# ProPrj_SmartOvi_v1_2025-12-15.net
KiCad netlist of a schematic drawn in EasyEDA Pro
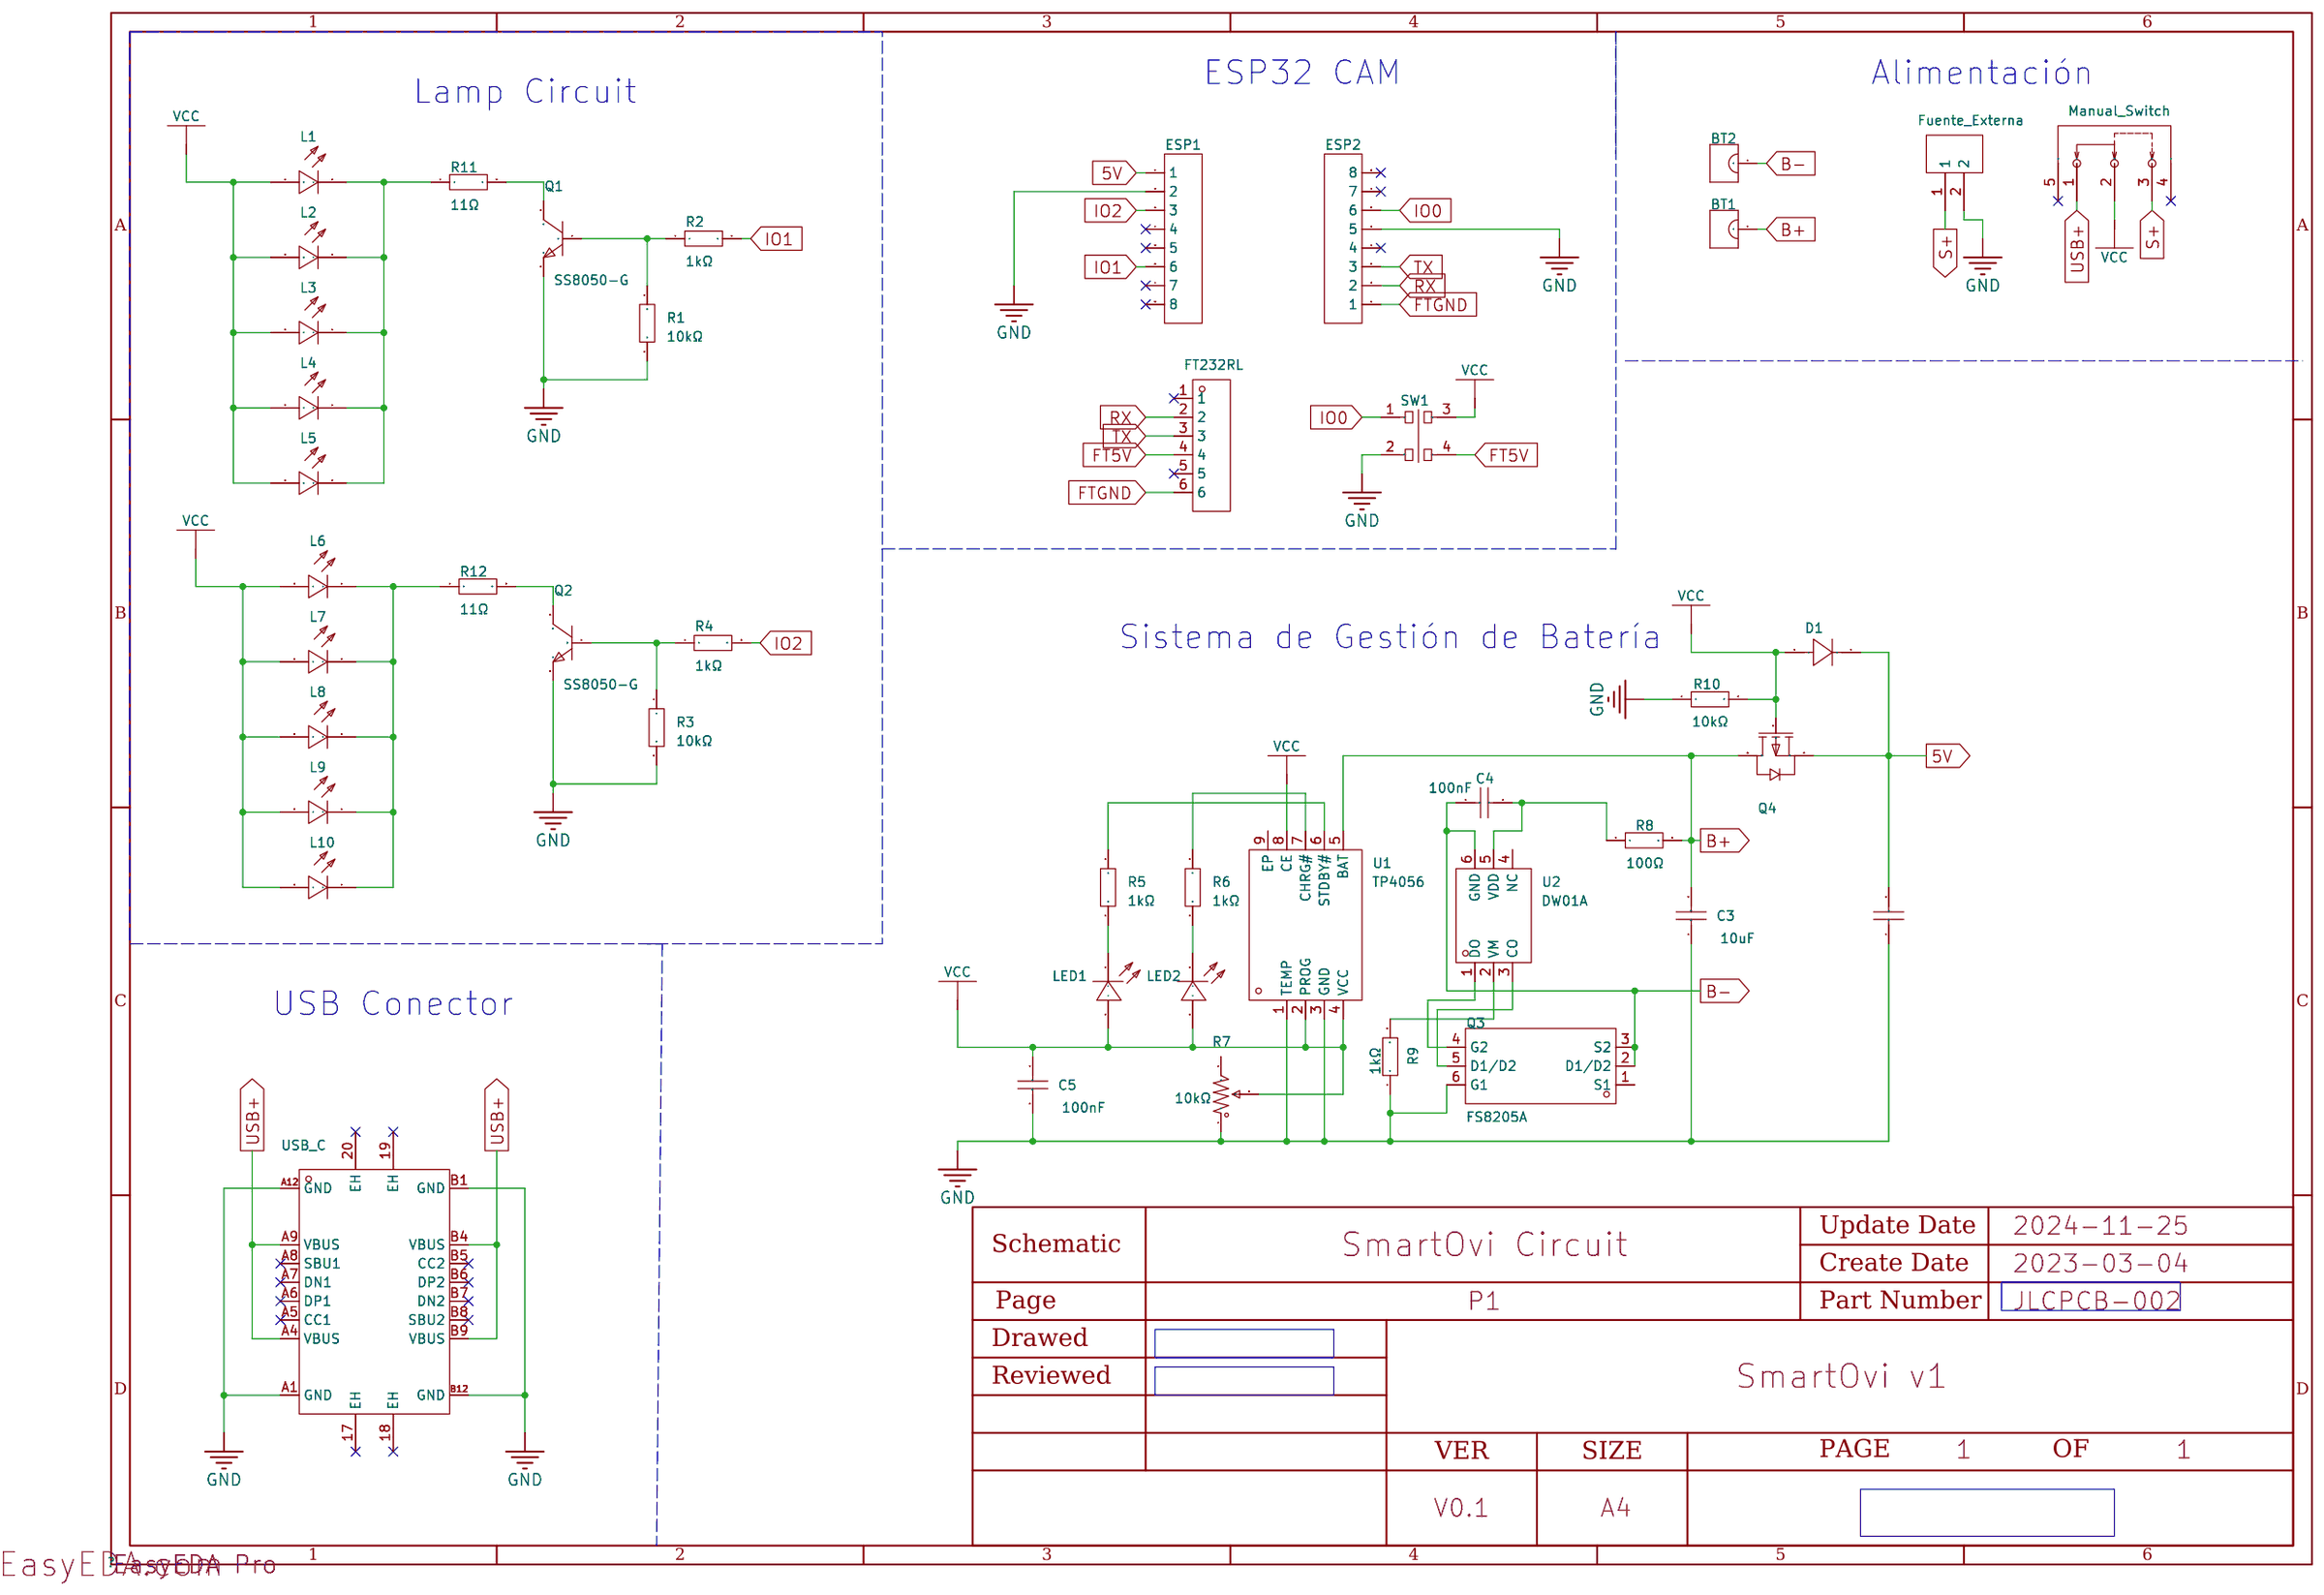
[diagram p0: schematic sheet]

(export (version "E")
  (design (tool "Eeschema 10.0.6"))
  (components
    (comp (ref "BT1")
      (value "MY-18650-01")
      (footprint "easyedapro:BAT-TH_MY-18650-01")
      (fields (field (name "Manufacturer") "MYOUNG(美阳)"))
      (libsource (lib "easyedapro") (part "MY-18650-01"))
    )
    (comp (ref "BT2")
      (value "MY-18650-01")
      (footprint "easyedapro:BAT-TH_MY-18650-01")
      (fields (field (name "Manufacturer") "MYOUNG(美阳)"))
      (libsource (lib "easyedapro") (part "MY-18650-01"))
    )
    (comp (ref "C1")
      (value "10uF")
      (footprint "easyedapro:C0805")
      (fields
        (field (name "Manufacturer Part") "CL21A106KPFNNNE")
        (field (name "Manufacturer") "SAMSUNG(三星)")
      )
      (libsource (lib "easyedapro") (part "CL21A106KPFNNNE"))
    )
    (comp (ref "C3")
      (value "10uF")
      (footprint "easyedapro:C0805")
      (fields
        (field (name "Manufacturer Part") "CL21A106KPFNNNE")
        (field (name "Manufacturer") "SAMSUNG(三星)")
      )
      (libsource (lib "easyedapro") (part "CL21A106KPFNNNE"))
    )
    (comp (ref "C4")
      (value "100nF")
      (footprint "easyedapro:C0805")
      (fields (field (name "Manufacturer Part") "0805B104K500NT") (field (name "Manufacturer") "FH(风华)"))
      (libsource (lib "easyedapro") (part "0805B104K500NT"))
    )
    (comp (ref "C5")
      (value "100nF")
      (footprint "easyedapro:C0805")
      (fields (field (name "Manufacturer Part") "0805B104K500NT") (field (name "Manufacturer") "FH(风华)"))
      (libsource (lib "easyedapro") (part "0805B104K500NT"))
    )
    (comp (ref "D1")
      (value "VS-90EPS16L-M3")
      (footprint "easyedapro:TO-247AD-2_L16.0-W5.0-P10.92-L")
      (fields (field (name "Manufacturer") "VISHAY(威世)"))
      (libsource (lib "easyedapro") (part "VS-90EPS16L-M3"))
    )
    (comp (ref "ESP1")
      (value "2.54-1*8P母环保")
      (footprint "easyedapro:HDR-TH_8P-P2.54-V-F-1")
      (fields (field (name "Manufacturer") "BOOMELE(博穆精密)"))
      (libsource (lib "easyedapro") (part "Header-Female-2.54_1x8"))
    )
    (comp (ref "ESP2")
      (value "2.54-1*8P母环保")
      (footprint "easyedapro:HDR-TH_8P-P2.54-V-F-1")
      (fields (field (name "Manufacturer") "BOOMELE(博穆精密)"))
      (libsource (lib "easyedapro") (part "Header-Female-2.54_1x8"))
    )
    (comp (ref "FT232RL")
      (value "2.54-1*6P母")
      (footprint "easyedapro:HDR-TH_6P-P2.54-V-F")
      (fields (field (name "Manufacturer") "BOOMELE(博穆精密)"))
      (libsource (lib "easyedapro") (part "Header-Female-2.54_1x6"))
    )
    (comp (ref "Fuente_Externa")
      (value "WJ500V-5.08-2P")
      (footprint "easyedapro:CONN-TH_2P-P5.00_WJ500V-5.08-2P")
      (fields (field (name "Manufacturer") "KANGNEX(康奈克斯电气)"))
      (libsource (lib "easyedapro") (part "WJ500V-5.08-2P-14-00A"))
    )
    (comp (ref "L1")
      (value "MHL5013UGDWT")
      (footprint "easyedapro:LED-TH_BD5.8-P2.54-RD")
      (fields (field (name "Manufacturer") "MEIHUA(美华)"))
      (libsource (lib "easyedapro") (part "MHL5013UGDWT"))
    )
    (comp (ref "L2")
      (value "MHL5013UGDWT")
      (footprint "easyedapro:LED-TH_BD5.8-P2.54-RD")
      (fields (field (name "Manufacturer") "MEIHUA(美华)"))
      (libsource (lib "easyedapro") (part "MHL5013UGDWT"))
    )
    (comp (ref "L3")
      (value "MHL5013UGDWT")
      (footprint "easyedapro:LED-TH_BD5.8-P2.54-RD")
      (fields (field (name "Manufacturer") "MEIHUA(美华)"))
      (libsource (lib "easyedapro") (part "MHL5013UGDWT"))
    )
    (comp (ref "L4")
      (value "MHL5013UGDWT")
      (footprint "easyedapro:LED-TH_BD5.8-P2.54-RD")
      (fields (field (name "Manufacturer") "MEIHUA(美华)"))
      (libsource (lib "easyedapro") (part "MHL5013UGDWT"))
    )
    (comp (ref "L5")
      (value "MHL5013UGDWT")
      (footprint "easyedapro:LED-TH_BD5.8-P2.54-RD")
      (fields (field (name "Manufacturer") "MEIHUA(美华)"))
      (libsource (lib "easyedapro") (part "MHL5013UGDWT"))
    )
    (comp (ref "L6")
      (value "MHL5013UGDWT")
      (footprint "easyedapro:LED-TH_BD5.8-P2.54-RD")
      (fields (field (name "Manufacturer") "MEIHUA(美华)"))
      (libsource (lib "easyedapro") (part "MHL5013UGDWT"))
    )
    (comp (ref "L7")
      (value "MHL5013UGDWT")
      (footprint "easyedapro:LED-TH_BD5.8-P2.54-RD")
      (fields (field (name "Manufacturer") "MEIHUA(美华)"))
      (libsource (lib "easyedapro") (part "MHL5013UGDWT"))
    )
    (comp (ref "L8")
      (value "MHL5013UGDWT")
      (footprint "easyedapro:LED-TH_BD5.8-P2.54-RD")
      (fields (field (name "Manufacturer") "MEIHUA(美华)"))
      (libsource (lib "easyedapro") (part "MHL5013UGDWT"))
    )
    (comp (ref "L9")
      (value "MHL5013UGDWT")
      (footprint "easyedapro:LED-TH_BD5.8-P2.54-RD")
      (fields (field (name "Manufacturer") "MEIHUA(美华)"))
      (libsource (lib "easyedapro") (part "MHL5013UGDWT"))
    )
    (comp (ref "L10")
      (value "MHL5013UGDWT")
      (footprint "easyedapro:LED-TH_BD5.8-P2.54-RD")
      (fields (field (name "Manufacturer") "MEIHUA(美华)"))
      (libsource (lib "easyedapro") (part "MHL5013UGDWT"))
    )
    (comp (ref "LED1")
      (value "NCD0805R1")
      (footprint "easyedapro:LED0805-RD")
      (description "Emitted Color:红灯")
      (fields (field (name "Manufacturer") "国星光电"))
      (libsource (lib "easyedapro") (part "FC-2012HRK-620D"))
    )
    (comp (ref "LED2")
      (value "NCD0805B2")
      (footprint "easyedapro:LED0805-RD")
      (description "Emitted Color:blue")
      (fields (field (name "Manufacturer") "国星光电"))
      (libsource (lib "easyedapro") (part "FC-A2012BK-470H2"))
    )
    (comp (ref "Manual_Switch")
      (value "SK12D07VG4")
      (footprint "easyedapro:SW-TH_SK12D07VG4")
      (fields (field (name "Manufacturer") "SHOU HAN(首韩)"))
      (libsource (lib "easyedapro") (part "SK12D07VG4"))
    )
    (comp (ref "Q1")
      (value "SS8050-G")
      (footprint "easyedapro:SOT-23-3_L2.9-W1.6-P1.90-LS2.8-BR")
      (fields (field (name "Manufacturer") "CJ(江苏长电/长晶)"))
      (libsource (lib "easyedapro") (part "SS8050-G"))
    )
    (comp (ref "Q2")
      (value "SS8050-G")
      (footprint "easyedapro:SOT-23-3_L2.9-W1.6-P1.90-LS2.8-BR")
      (fields (field (name "Manufacturer") "CJ(江苏长电/长晶)"))
      (libsource (lib "easyedapro") (part "SS8050-G"))
    )
    (comp (ref "Q3")
      (value "FS8205A")
      (footprint "easyedapro:SOT-23-6_L2.9-W1.6-P0.95-LS2.8-BR")
      (fields (field (name "Manufacturer") "FUXINSEMI(富芯森美)"))
      (libsource (lib "easyedapro") (part "FS8205A_C908265"))
    )
    (comp (ref "Q4")
      (value "AO3401A")
      (footprint "easyedapro:SOT-23_L2.9-W1.3-P1.90-LS2.4-BR")
      (fields (field (name "Manufacturer") "UMW(广东友台半导体)"))
      (libsource (lib "easyedapro") (part "AO3401A_C347476"))
    )
    (comp (ref "R1")
      (value "10kΩ")
      (footprint "easyedapro:R0805")
      (fields
        (field (name "Manufacturer Part") "0805W8J0103T5E")
        (field (name "Manufacturer") "UNI-ROYAL(厚声)")
      )
      (libsource (lib "easyedapro") (part "0805W8J0103T5E"))
    )
    (comp (ref "R2")
      (value "1kΩ")
      (footprint "easyedapro:R0805")
      (fields
        (field (name "Manufacturer Part") "0805W8J0102T5E")
        (field (name "Manufacturer") "UNI-ROYAL(厚声)")
      )
      (libsource (lib "easyedapro") (part "0805W8J0102T5E"))
    )
    (comp (ref "R3")
      (value "10kΩ")
      (footprint "easyedapro:R0805")
      (fields
        (field (name "Manufacturer Part") "0805W8J0103T5E")
        (field (name "Manufacturer") "UNI-ROYAL(厚声)")
      )
      (libsource (lib "easyedapro") (part "0805W8J0103T5E"))
    )
    (comp (ref "R4")
      (value "1kΩ")
      (footprint "easyedapro:R0805")
      (fields
        (field (name "Manufacturer Part") "0805W8J0102T5E")
        (field (name "Manufacturer") "UNI-ROYAL(厚声)")
      )
      (libsource (lib "easyedapro") (part "0805W8J0102T5E"))
    )
    (comp (ref "R5")
      (value "1kΩ")
      (footprint "easyedapro:R0805")
      (fields
        (field (name "Manufacturer Part") "0805W8J0102T5E")
        (field (name "Manufacturer") "UNI-ROYAL(厚声)")
      )
      (libsource (lib "easyedapro") (part "0805W8J0102T5E"))
    )
    (comp (ref "R6")
      (value "1kΩ")
      (footprint "easyedapro:R0805")
      (fields
        (field (name "Manufacturer Part") "0805W8J0102T5E")
        (field (name "Manufacturer") "UNI-ROYAL(厚声)")
      )
      (libsource (lib "easyedapro") (part "0805W8J0102T5E"))
    )
    (comp (ref "R7")
      (value "10kΩ")
      (footprint "easyedapro:RES-ADJ-SMD_3P-L3.0-W3.8-P1.75-BR")
      (description "Resistance: Tolerance:±25% Tolerance:±25% Power(Watts):150mW Turns:- Rated Voltage:-")
      (fields (field (name "Manufacturer Part") "TC33X-2-103E") (field (name "Manufacturer") "BOURNS"))
      (libsource (lib "easyedapro") (part "TC33X-2-103E"))
    )
    (comp (ref "R8")
      (value "100Ω")
      (footprint "easyedapro:R0805")
      (fields (field (name "Manufacturer Part") "RTT05101JTP") (field (name "Manufacturer") "RALEC(旺诠)"))
      (libsource (lib "easyedapro") (part "RTT05101JTP"))
    )
    (comp (ref "R9")
      (value "1kΩ")
      (footprint "easyedapro:R0805")
      (fields
        (field (name "Manufacturer Part") "0805W8J0102T5E")
        (field (name "Manufacturer") "UNI-ROYAL(厚声)")
      )
      (libsource (lib "easyedapro") (part "0805W8J0102T5E"))
    )
    (comp (ref "R10")
      (value "10kΩ")
      (footprint "easyedapro:R0805")
      (fields
        (field (name "Manufacturer Part") "0805W8J0103T5E")
        (field (name "Manufacturer") "UNI-ROYAL(厚声)")
      )
      (libsource (lib "easyedapro") (part "0805W8J0103T5E"))
    )
    (comp (ref "R11")
      (value "11Ω")
      (footprint "easyedapro:R0805")
      (fields (field (name "Manufacturer Part") "AECR0805F11R0K9") (field (name "Manufacturer") "RESI(开步睿思)"))
      (libsource (lib "easyedapro") (part "AECR0805F11R0K9"))
    )
    (comp (ref "R12")
      (value "11Ω")
      (footprint "easyedapro:R0805")
      (fields (field (name "Manufacturer Part") "AECR0805F11R0K9") (field (name "Manufacturer") "RESI(开步睿思)"))
      (libsource (lib "easyedapro") (part "AECR0805F11R0K9"))
    )
    (comp (ref "SW1")
      (value "BTSA-L-P-11")
      (footprint "easyedapro:SW-TH_BTSA-X-P-11")
      (fields (field (name "Manufacturer") "ROCPU Switches(台普)"))
      (libsource (lib "easyedapro") (part "BTSA-N-P-11"))
    )
    (comp (ref "U1")
      (value "TP4056")
      (footprint "easyedapro:ESOP-8_L4.9-W3.9-P1.27-LS6.0-BL-EP")
      (fields (field (name "Manufacturer") "TECH PUBLIC(台舟)"))
      (libsource (lib "easyedapro") (part "TP4056_C5311018"))
    )
    (comp (ref "U2")
      (value "DW01A")
      (footprint "easyedapro:SOT-23-6_L2.9-W1.6-P0.95-LS2.8-BL")
      (fields (field (name "Manufacturer") "TF(拓锋)"))
      (libsource (lib "easyedapro") (part "DW01A_C436931"))
    )
    (comp (ref "USB_C")
      (value "TYPEC-306DDW-ARP16")
      (footprint "easyedapro:USB-C-TH_TYPEC-306DDW-ARP16")
      (fields (field (name "Manufacturer") "XUNPU(讯普)"))
      (libsource (lib "easyedapro") (part "TYPEC-306DDW-ARP16"))
    )
  )
  (nets
    (net (code "1") (name "5V") (class "Default")
      (node (ref "C1") (pin "2") (pinfunction "2_2") (pintype "input"))
      (node (ref "D1") (pin "1") (pinfunction "K_1") (pintype "unspecified"))
      (node (ref "ESP1") (pin "1") (pinfunction "1_1") (pintype "input"))
      (node (ref "Q4") (pin "2") (pinfunction "S_2") (pintype "input"))
    )
    (net (code "2") (name "B+") (class "Default")
      (node (ref "BT1") (pin "1") (pinfunction "1_1") (pintype "input"))
      (node (ref "C3") (pin "2") (pinfunction "2_2") (pintype "input"))
      (node (ref "Q4") (pin "3") (pinfunction "D_3") (pintype "input"))
      (node (ref "R8") (pin "2") (pinfunction "2_2") (pintype "input"))
      (node (ref "U1") (pin "5") (pinfunction "BAT_5") (pintype "input"))
    )
    (net (code "3") (name "B-") (class "Default")
      (node (ref "BT2") (pin "1") (pinfunction "1_1") (pintype "input"))
      (node (ref "C4") (pin "1") (pinfunction "1_1") (pintype "input"))
      (node (ref "Q3") (pin "2") (pinfunction "D1/D2_2") (pintype "input"))
      (node (ref "Q3") (pin "3") (pinfunction "S2_3") (pintype "input"))
      (node (ref "U2") (pin "6") (pinfunction "GND_6") (pintype "input"))
    )
    (net (code "4") (name "FT5V") (class "Default")
      (node (ref "FT232RL") (pin "4") (pinfunction "4_4") (pintype "input"))
      (node (ref "SW1") (pin "4") (pinfunction "4_4") (pintype "input"))
    )
    (net (code "5") (name "FTGND") (class "Default")
      (node (ref "ESP2") (pin "1") (pinfunction "1_1") (pintype "input"))
      (node (ref "FT232RL") (pin "6") (pinfunction "6_6") (pintype "input"))
    )
    (net (code "6") (name "GND") (class "Default")
      (node (ref "C1") (pin "1") (pinfunction "1_1") (pintype "input"))
      (node (ref "C3") (pin "1") (pinfunction "1_1") (pintype "input"))
      (node (ref "C5") (pin "2") (pinfunction "2_2") (pintype "input"))
      (node (ref "ESP1") (pin "2") (pinfunction "2_2") (pintype "input"))
      (node (ref "ESP2") (pin "5") (pinfunction "5_5") (pintype "input"))
      (node (ref "Fuente_Externa") (pin "2") (pinfunction "2_2") (pintype "input"))
      (node (ref "Q1") (pin "2") (pinfunction "E_2") (pintype "input"))
      (node (ref "Q2") (pin "2") (pinfunction "E_2") (pintype "input"))
      (node (ref "Q3") (pin "6") (pinfunction "G1_6") (pintype "input"))
      (node (ref "R1") (pin "2") (pinfunction "2_2") (pintype "input"))
      (node (ref "R10") (pin "1") (pinfunction "1_1") (pintype "input"))
      (node (ref "R3") (pin "2") (pinfunction "2_2") (pintype "input"))
      (node (ref "R7") (pin "1") (pinfunction "1_1") (pintype "input"))
      (node (ref "R9") (pin "1") (pinfunction "1_1") (pintype "input"))
      (node (ref "SW1") (pin "2") (pinfunction "2_2") (pintype "input"))
      (node (ref "U1") (pin "1") (pinfunction "TEMP_1") (pintype "input"))
      (node (ref "U1") (pin "3") (pinfunction "GND_3") (pintype "input"))
      (node (ref "USB_C") (pin "A1") (pinfunction "GND_A1") (pintype "input"))
      (node (ref "USB_C") (pin "A12") (pinfunction "GND_A12") (pintype "input"))
      (node (ref "USB_C") (pin "B1") (pinfunction "GND_B1") (pintype "input"))
      (node (ref "USB_C") (pin "B12") (pinfunction "GND_B12") (pintype "input"))
    )
    (net (code "7") (name "IO0") (class "Default")
      (node (ref "ESP2") (pin "6") (pinfunction "6_6") (pintype "input"))
      (node (ref "SW1") (pin "1") (pinfunction "1_1") (pintype "input"))
    )
    (net (code "8") (name "IO1") (class "Default")
      (node (ref "ESP1") (pin "6") (pinfunction "6_6") (pintype "input"))
      (node (ref "R2") (pin "2") (pinfunction "2_2") (pintype "input"))
    )
    (net (code "9") (name "IO2") (class "Default")
      (node (ref "ESP1") (pin "3") (pinfunction "3_3") (pintype "input"))
      (node (ref "R4") (pin "2") (pinfunction "2_2") (pintype "input"))
    )
    (net (code "10") (name "Net-(L1-K)") (class "Default")
      (node (ref "L1") (pin "1") (pinfunction "K_1") (pintype "input"))
      (node (ref "L2") (pin "1") (pinfunction "K_1") (pintype "input"))
      (node (ref "L3") (pin "1") (pinfunction "K_1") (pintype "input"))
      (node (ref "L4") (pin "1") (pinfunction "K_1") (pintype "input"))
      (node (ref "L5") (pin "1") (pinfunction "K_1") (pintype "input"))
      (node (ref "R11") (pin "1") (pinfunction "1_1") (pintype "unspecified"))
    )
    (net (code "11") (name "Net-(L10-K)") (class "Default")
      (node (ref "L10") (pin "1") (pinfunction "K_1") (pintype "input"))
      (node (ref "L6") (pin "1") (pinfunction "K_1") (pintype "input"))
      (node (ref "L7") (pin "1") (pinfunction "K_1") (pintype "input"))
      (node (ref "L8") (pin "1") (pinfunction "K_1") (pintype "input"))
      (node (ref "L9") (pin "1") (pinfunction "K_1") (pintype "input"))
      (node (ref "R12") (pin "1") (pinfunction "1_1") (pintype "unspecified"))
    )
    (net (code "12") (name "Net-(LED1--)") (class "Default")
      (node (ref "LED1") (pin "1") (pinfunction "-_1") (pintype "input"))
      (node (ref "R5") (pin "1") (pinfunction "1_1") (pintype "input"))
    )
    (net (code "13") (name "Net-(LED2--)") (class "Default")
      (node (ref "LED2") (pin "1") (pinfunction "-_1") (pintype "input"))
      (node (ref "R6") (pin "1") (pinfunction "1_1") (pintype "input"))
    )
    (net (code "14") (name "Net-(Q1-B)") (class "Default")
      (node (ref "Q1") (pin "1") (pinfunction "B_1") (pintype "input"))
      (node (ref "R1") (pin "1") (pinfunction "1_1") (pintype "input"))
      (node (ref "R2") (pin "1") (pinfunction "1_1") (pintype "input"))
    )
    (net (code "15") (name "Net-(Q1-C)") (class "Default")
      (node (ref "Q1") (pin "3") (pinfunction "C_3") (pintype "input"))
      (node (ref "R11") (pin "2") (pinfunction "2_2") (pintype "unspecified"))
    )
    (net (code "16") (name "Net-(Q2-B)") (class "Default")
      (node (ref "Q2") (pin "1") (pinfunction "B_1") (pintype "input"))
      (node (ref "R3") (pin "1") (pinfunction "1_1") (pintype "input"))
      (node (ref "R4") (pin "1") (pinfunction "1_1") (pintype "input"))
    )
    (net (code "17") (name "Net-(Q2-C)") (class "Default")
      (node (ref "Q2") (pin "3") (pinfunction "C_3") (pintype "input"))
      (node (ref "R12") (pin "2") (pinfunction "2_2") (pintype "unspecified"))
    )
    (net (code "18") (name "Net-(Q3-G2)") (class "Default")
      (node (ref "Q3") (pin "4") (pinfunction "G2_4") (pintype "input"))
      (node (ref "U2") (pin "1") (pinfunction "DO_1") (pintype "input"))
    )
    (net (code "19") (name "Net-(U1-CHRG#)") (class "Default")
      (node (ref "R6") (pin "2") (pinfunction "2_2") (pintype "input"))
      (node (ref "U1") (pin "7") (pinfunction "CHRG#_7") (pintype "input"))
    )
    (net (code "20") (name "Net-(U1-STDBY#)") (class "Default")
      (node (ref "R5") (pin "2") (pinfunction "2_2") (pintype "input"))
      (node (ref "U1") (pin "6") (pinfunction "STDBY#_6") (pintype "input"))
    )
    (net (code "21") (name "Net-(U2-CO)") (class "Default")
      (node (ref "Q3") (pin "5") (pinfunction "D1/D2_5") (pintype "input"))
      (node (ref "U2") (pin "3") (pinfunction "CO_3") (pintype "input"))
    )
    (net (code "22") (name "Net-(U2-VDD)") (class "Default")
      (node (ref "C4") (pin "2") (pinfunction "2_2") (pintype "input"))
      (node (ref "R8") (pin "1") (pinfunction "1_1") (pintype "input"))
      (node (ref "U2") (pin "5") (pinfunction "VDD_5") (pintype "input"))
    )
    (net (code "23") (name "Net-(U2-VM)") (class "Default")
      (node (ref "R9") (pin "2") (pinfunction "2_2") (pintype "input"))
      (node (ref "U2") (pin "2") (pinfunction "VM_2") (pintype "input"))
    )
    (net (code "24") (name "RX") (class "Default")
      (node (ref "ESP2") (pin "2") (pinfunction "2_2") (pintype "input"))
      (node (ref "FT232RL") (pin "2") (pinfunction "2_2") (pintype "input"))
    )
    (net (code "25") (name "S+") (class "Default")
      (node (ref "Fuente_Externa") (pin "1") (pinfunction "1_1") (pintype "input"))
      (node (ref "Manual_Switch") (pin "3") (pinfunction "3_3") (pintype "input"))
    )
    (net (code "26") (name "TX") (class "Default")
      (node (ref "ESP2") (pin "3") (pinfunction "3_3") (pintype "input"))
      (node (ref "FT232RL") (pin "3") (pinfunction "3_3") (pintype "input"))
    )
    (net (code "27") (name "USB+") (class "Default")
      (node (ref "Manual_Switch") (pin "1") (pinfunction "1_1") (pintype "input"))
      (node (ref "USB_C") (pin "A4") (pinfunction "VBUS_A4") (pintype "input"))
      (node (ref "USB_C") (pin "A9") (pinfunction "VBUS_A9") (pintype "input"))
      (node (ref "USB_C") (pin "B4") (pinfunction "VBUS_B4") (pintype "input"))
      (node (ref "USB_C") (pin "B9") (pinfunction "VBUS_B9") (pintype "input"))
    )
    (net (code "28") (name "VCC") (class "Default")
      (node (ref "C5") (pin "1") (pinfunction "1_1") (pintype "input"))
      (node (ref "D1") (pin "3") (pinfunction "A_3") (pintype "unspecified"))
      (node (ref "L1") (pin "2") (pinfunction "A_2") (pintype "input"))
      (node (ref "L10") (pin "2") (pinfunction "A_2") (pintype "input"))
      (node (ref "L2") (pin "2") (pinfunction "A_2") (pintype "input"))
      (node (ref "L3") (pin "2") (pinfunction "A_2") (pintype "input"))
      (node (ref "L4") (pin "2") (pinfunction "A_2") (pintype "input"))
      (node (ref "L5") (pin "2") (pinfunction "A_2") (pintype "input"))
      (node (ref "L6") (pin "2") (pinfunction "A_2") (pintype "input"))
      (node (ref "L7") (pin "2") (pinfunction "A_2") (pintype "input"))
      (node (ref "L8") (pin "2") (pinfunction "A_2") (pintype "input"))
      (node (ref "L9") (pin "2") (pinfunction "A_2") (pintype "input"))
      (node (ref "LED1") (pin "2") (pinfunction "+_2") (pintype "input"))
      (node (ref "LED2") (pin "2") (pinfunction "+_2") (pintype "input"))
      (node (ref "Manual_Switch") (pin "2") (pinfunction "2_2") (pintype "input"))
      (node (ref "Q4") (pin "1") (pinfunction "G_1") (pintype "input"))
      (node (ref "R10") (pin "2") (pinfunction "2_2") (pintype "input"))
      (node (ref "R7") (pin "2") (pinfunction "2_2") (pintype "input"))
      (node (ref "SW1") (pin "3") (pinfunction "3_3") (pintype "input"))
      (node (ref "U1") (pin "2") (pinfunction "PROG_2") (pintype "input"))
      (node (ref "U1") (pin "4") (pinfunction "VCC_4") (pintype "input"))
      (node (ref "U1") (pin "8") (pinfunction "CE_8") (pintype "input"))
    )
    (net (code "29") (name "unconnected-(ESP1-Pad4)") (class "Default")
      (node (ref "ESP1") (pin "4") (pinfunction "4_4") (pintype "input+no_connect"))
    )
    (net (code "30") (name "unconnected-(ESP1-Pad5)") (class "Default")
      (node (ref "ESP1") (pin "5") (pinfunction "5_5") (pintype "input+no_connect"))
    )
    (net (code "31") (name "unconnected-(ESP1-Pad7)") (class "Default")
      (node (ref "ESP1") (pin "7") (pinfunction "7_7") (pintype "input+no_connect"))
    )
    (net (code "32") (name "unconnected-(ESP1-Pad8)") (class "Default")
      (node (ref "ESP1") (pin "8") (pinfunction "8_8") (pintype "input+no_connect"))
    )
    (net (code "33") (name "unconnected-(ESP2-Pad4)") (class "Default")
      (node (ref "ESP2") (pin "4") (pinfunction "4_4") (pintype "input+no_connect"))
    )
    (net (code "34") (name "unconnected-(ESP2-Pad7)") (class "Default")
      (node (ref "ESP2") (pin "7") (pinfunction "7_7") (pintype "input+no_connect"))
    )
    (net (code "35") (name "unconnected-(ESP2-Pad8)") (class "Default")
      (node (ref "ESP2") (pin "8") (pinfunction "8_8") (pintype "input+no_connect"))
    )
    (net (code "36") (name "unconnected-(FT232RL-Pad1)") (class "Default")
      (node (ref "FT232RL") (pin "1") (pinfunction "1_1") (pintype "input+no_connect"))
    )
    (net (code "37") (name "unconnected-(FT232RL-Pad5)") (class "Default")
      (node (ref "FT232RL") (pin "5") (pinfunction "5_5") (pintype "input+no_connect"))
    )
    (net (code "38") (name "unconnected-(Manual_Switch-Pad4)") (class "Default")
      (node (ref "Manual_Switch") (pin "4") (pinfunction "4_4") (pintype "input+no_connect"))
    )
    (net (code "39") (name "unconnected-(Manual_Switch-Pad5)") (class "Default")
      (node (ref "Manual_Switch") (pin "5") (pinfunction "5_5") (pintype "input+no_connect"))
    )
    (net (code "40") (name "unconnected-(Q3-S1-Pad1)") (class "Default")
      (node (ref "Q3") (pin "1") (pinfunction "S1_1") (pintype "input"))
    )
    (net (code "41") (name "unconnected-(R7-Pad3)") (class "Default")
      (node (ref "R7") (pin "3") (pinfunction "3_3") (pintype "input"))
    )
    (net (code "42") (name "unconnected-(U1-EP-Pad9)") (class "Default")
      (node (ref "U1") (pin "9") (pinfunction "EP_9") (pintype "input"))
    )
    (net (code "43") (name "unconnected-(U2-NC-Pad4)") (class "Default")
      (node (ref "U2") (pin "4") (pinfunction "NC_4") (pintype "input"))
    )
    (net (code "44") (name "unconnected-(USB_C-CC1-PadA5)") (class "Default")
      (node (ref "USB_C") (pin "A5") (pinfunction "CC1_A5") (pintype "input+no_connect"))
    )
    (net (code "45") (name "unconnected-(USB_C-CC2-PadB5)") (class "Default")
      (node (ref "USB_C") (pin "B5") (pinfunction "CC2_B5") (pintype "input+no_connect"))
    )
    (net (code "46") (name "unconnected-(USB_C-DN1-PadA7)") (class "Default")
      (node (ref "USB_C") (pin "A7") (pinfunction "DN1_A7") (pintype "input+no_connect"))
    )
    (net (code "47") (name "unconnected-(USB_C-DN2-PadB7)") (class "Default")
      (node (ref "USB_C") (pin "B7") (pinfunction "DN2_B7") (pintype "input+no_connect"))
    )
    (net (code "48") (name "unconnected-(USB_C-DP1-PadA6)") (class "Default")
      (node (ref "USB_C") (pin "A6") (pinfunction "DP1_A6") (pintype "input+no_connect"))
    )
    (net (code "49") (name "unconnected-(USB_C-DP2-PadB6)") (class "Default")
      (node (ref "USB_C") (pin "B6") (pinfunction "DP2_B6") (pintype "input+no_connect"))
    )
    (net (code "50") (name "unconnected-(USB_C-EH-Pad17)") (class "Default")
      (node (ref "USB_C") (pin "17") (pinfunction "EH_17") (pintype "input+no_connect"))
    )
    (net (code "51") (name "unconnected-(USB_C-EH-Pad18)") (class "Default")
      (node (ref "USB_C") (pin "18") (pinfunction "EH_18") (pintype "input+no_connect"))
    )
    (net (code "52") (name "unconnected-(USB_C-EH-Pad19)") (class "Default")
      (node (ref "USB_C") (pin "19") (pinfunction "EH_19") (pintype "input+no_connect"))
    )
    (net (code "53") (name "unconnected-(USB_C-EH-Pad20)") (class "Default")
      (node (ref "USB_C") (pin "20") (pinfunction "EH_20") (pintype "input+no_connect"))
    )
    (net (code "54") (name "unconnected-(USB_C-SBU1-PadA8)") (class "Default")
      (node (ref "USB_C") (pin "A8") (pinfunction "SBU1_A8") (pintype "input+no_connect"))
    )
    (net (code "55") (name "unconnected-(USB_C-SBU2-PadB8)") (class "Default")
      (node (ref "USB_C") (pin "B8") (pinfunction "SBU2_B8") (pintype "input+no_connect"))
    )
  )
)
